# Array-Sensors.net
KiCad netlist of a schematic drawn in Altium Designer
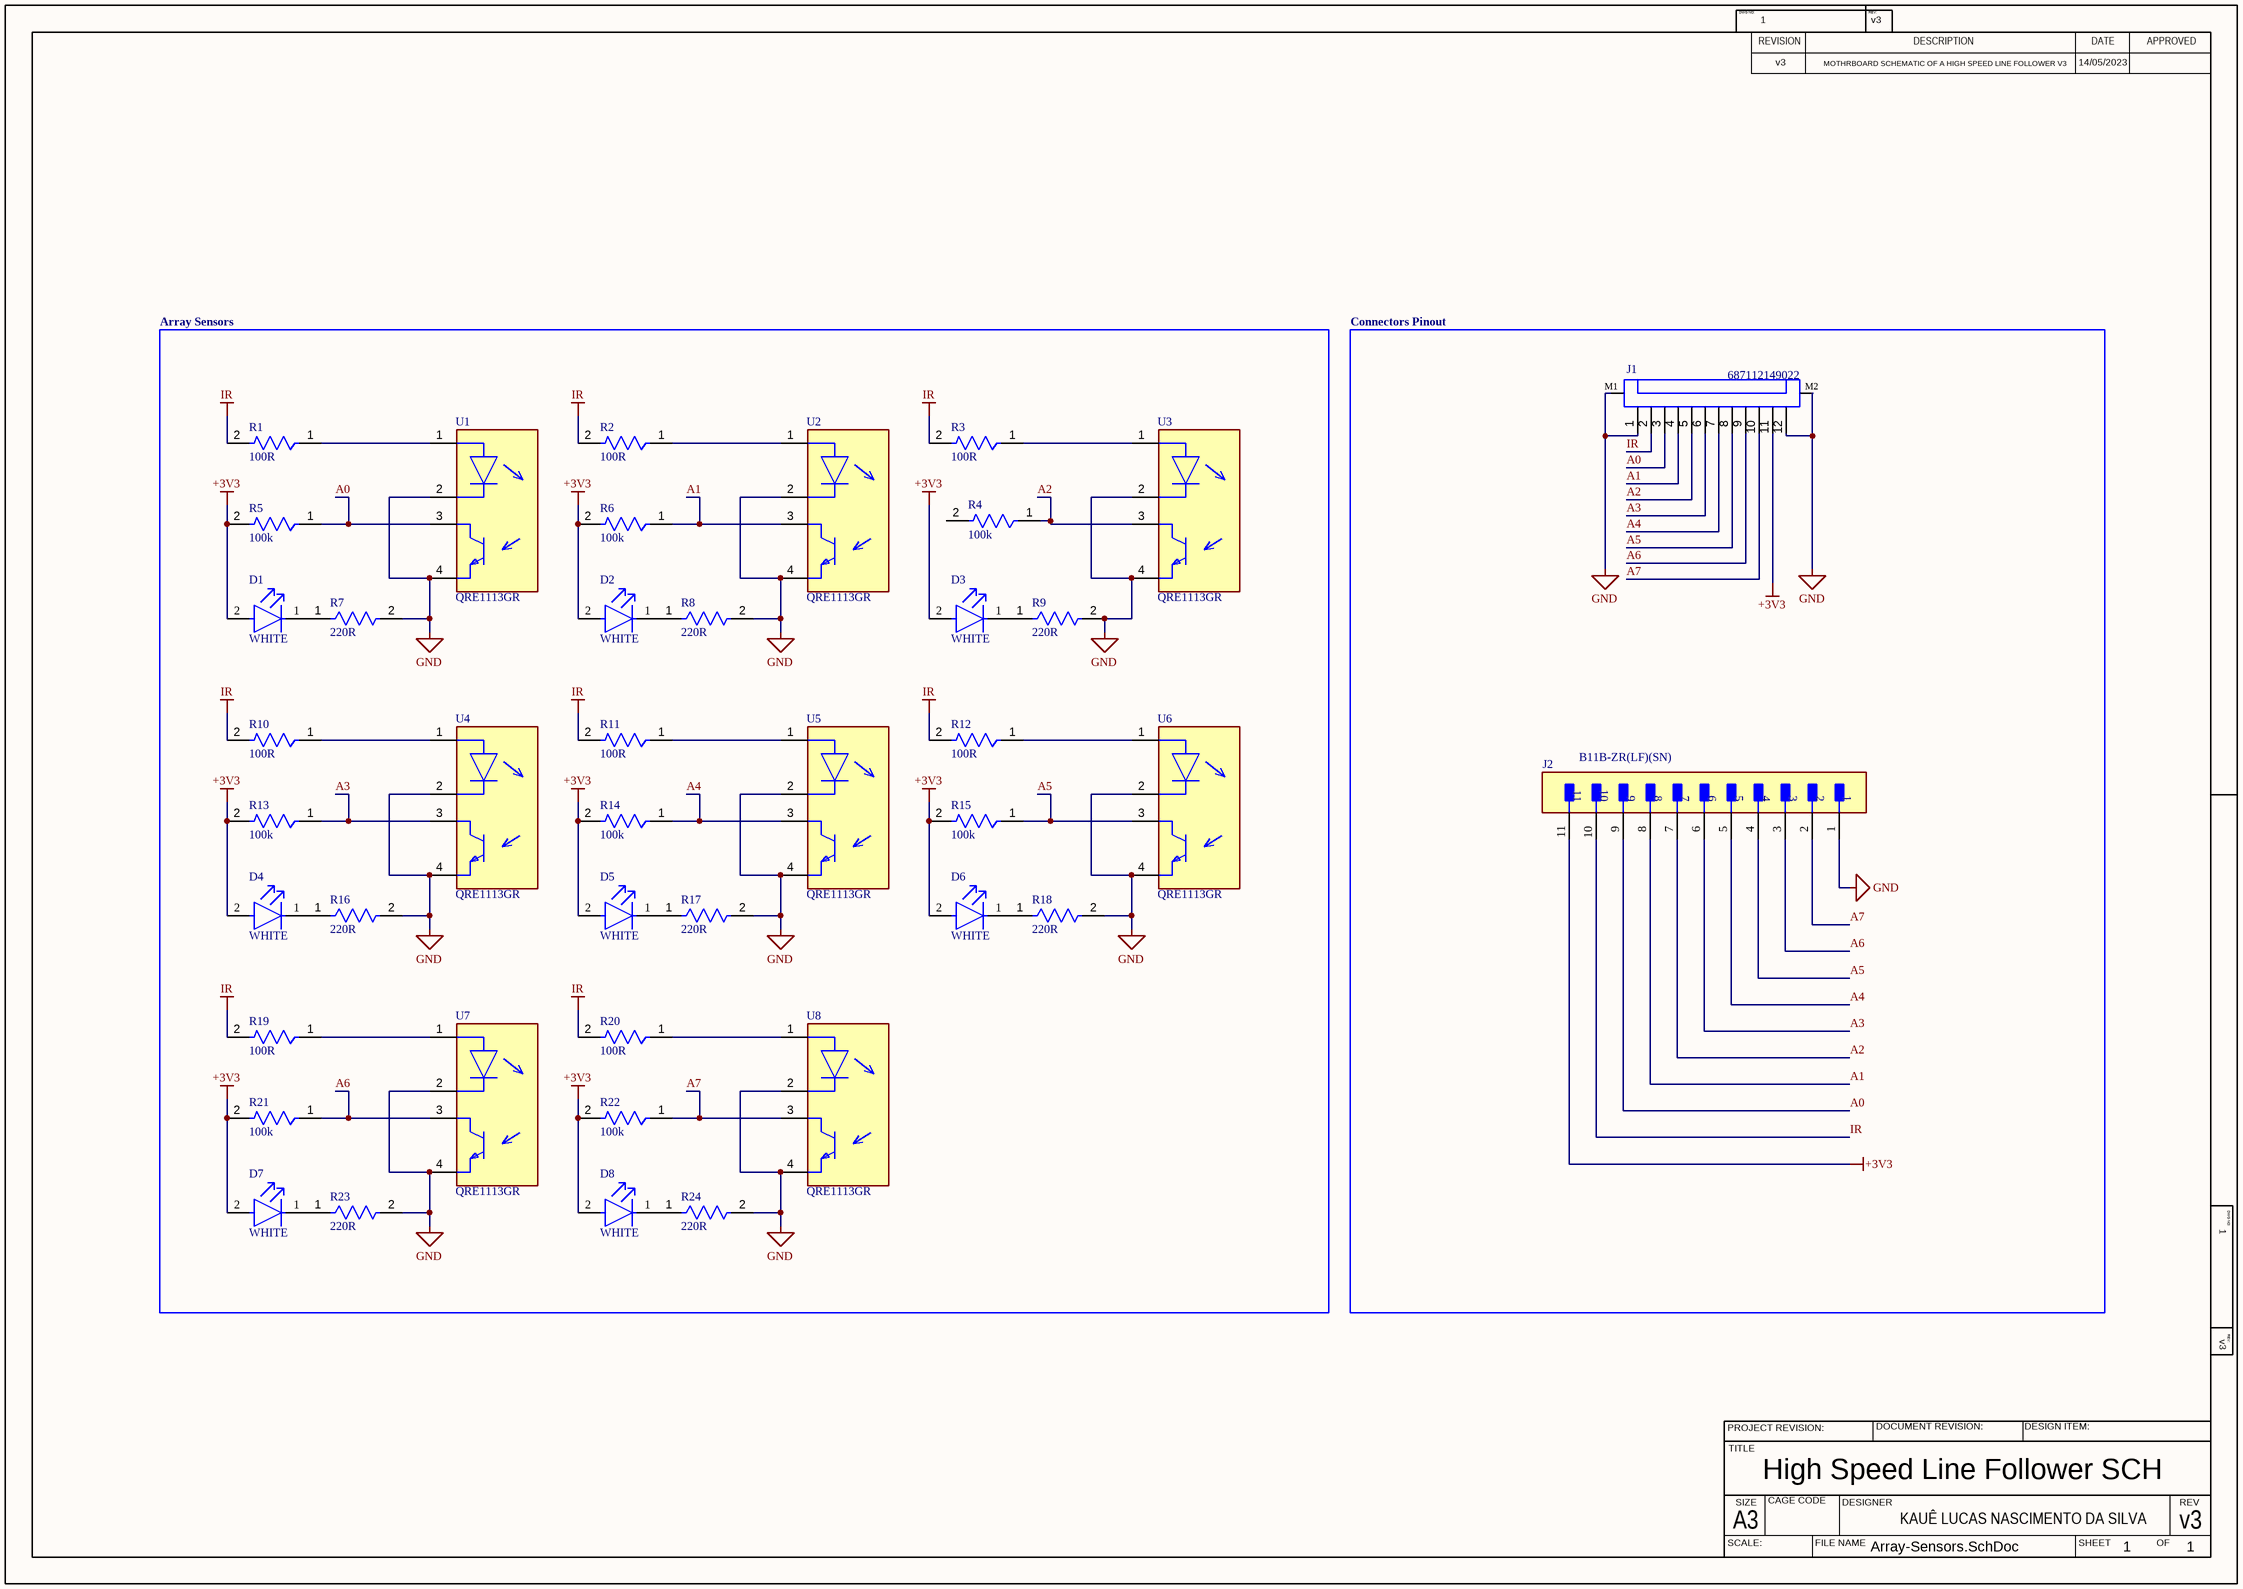
[diagram p0: Array-Sensors.SchDoc]

(export (version "E")
  (design (tool "Eeschema 10.0.6"))
  (components
    (comp (ref "D1")
      (value "WHITE")
      (footprint "FP-SML-LX0805UWC-TR-MFG")
      (description "SML-LX0805UWC-TR White LED, 0805 Diffused, Rectangle Lens SMD package")
      (libsource (lib "Altium Content Vault") (part "8706943c75ba83719d021d2fdc84c58"))
    )
    (comp (ref "D2")
      (value "WHITE")
      (footprint "FP-SML-LX0805UWC-TR-MFG")
      (description "SML-LX0805UWC-TR White LED, 0805 Diffused, Rectangle Lens SMD package")
      (libsource (lib "Altium Content Vault") (part "8706943c75ba83719d021d2fdc84c58"))
    )
    (comp (ref "D3")
      (value "WHITE")
      (footprint "FP-SML-LX0805UWC-TR-MFG")
      (description "SML-LX0805UWC-TR White LED, 0805 Diffused, Rectangle Lens SMD package")
      (libsource (lib "Altium Content Vault") (part "8706943c75ba83719d021d2fdc84c58"))
    )
    (comp (ref "D4")
      (value "WHITE")
      (footprint "FP-SML-LX0805UWC-TR-MFG")
      (description "SML-LX0805UWC-TR White LED, 0805 Diffused, Rectangle Lens SMD package")
      (libsource (lib "Altium Content Vault") (part "8706943c75ba83719d021d2fdc84c58"))
    )
    (comp (ref "D5")
      (value "WHITE")
      (footprint "FP-SML-LX0805UWC-TR-MFG")
      (description "SML-LX0805UWC-TR White LED, 0805 Diffused, Rectangle Lens SMD package")
      (libsource (lib "Altium Content Vault") (part "8706943c75ba83719d021d2fdc84c58"))
    )
    (comp (ref "D6")
      (value "WHITE")
      (footprint "FP-SML-LX0805UWC-TR-MFG")
      (description "SML-LX0805UWC-TR White LED, 0805 Diffused, Rectangle Lens SMD package")
      (libsource (lib "Altium Content Vault") (part "8706943c75ba83719d021d2fdc84c58"))
    )
    (comp (ref "D7")
      (value "WHITE")
      (footprint "FP-SML-LX0805UWC-TR-MFG")
      (description "SML-LX0805UWC-TR White LED, 0805 Diffused, Rectangle Lens SMD package")
      (libsource (lib "Altium Content Vault") (part "8706943c75ba83719d021d2fdc84c58"))
    )
    (comp (ref "D8")
      (value "WHITE")
      (footprint "FP-SML-LX0805UWC-TR-MFG")
      (description "SML-LX0805UWC-TR White LED, 0805 Diffused, Rectangle Lens SMD package")
      (libsource (lib "Altium Content Vault") (part "8706943c75ba83719d021d2fdc84c58"))
    )
    (comp (ref "J1")
      (value "687112149022")
      (footprint "687112149022")
      (description "FFC/FPC Connector, 12 Contact(s), 1 Row(s), Female, Right Angle, Surface Mount Terminal")
      (libsource (lib "Altium Content Vault") (part "FPC - 12P - 2MP"))
    )
    (comp (ref "J2")
      (value "B11B-ZR(LF)(SN)")
      (footprint "FP-B11B-ZR_LF_SN-MFG")
      (libsource (lib "Altium Content Vault") (part "f29d4bf112d7e9a430f8be9e77fc91e"))
    )
    (comp (ref "R1")
      (value "100R")
      (footprint "FP-AF0805-IPC_A")
      (description "Anti-Sulfurated Chip Resistor Automotive Grade 100Ω 5% 0.125W ±100ppm/°C 0805")
      (fields (field (name "TOLERANCE") "5%"))
      (libsource (lib "Altium Content Vault") (part "1029c3af85768c4190bb7ad29bc67b5"))
    )
    (comp (ref "R2")
      (value "100R")
      (footprint "FP-AF0805-IPC_A")
      (description "Anti-Sulfurated Chip Resistor Automotive Grade 100Ω 5% 0.125W ±100ppm/°C 0805")
      (fields (field (name "TOLERANCE") "5%"))
      (libsource (lib "Altium Content Vault") (part "1029c3af85768c4190bb7ad29bc67b5"))
    )
    (comp (ref "R3")
      (value "100R")
      (footprint "FP-AF0805-IPC_A")
      (description "Anti-Sulfurated Chip Resistor Automotive Grade 100Ω 5% 0.125W ±100ppm/°C 0805")
      (fields (field (name "TOLERANCE") "5%"))
      (libsource (lib "Altium Content Vault") (part "1029c3af85768c4190bb7ad29bc67b5"))
    )
    (comp (ref "R4")
      (value "100k")
      (footprint "FP-CRCW0805-HPe3-MFG")
      (description "RES Thick Film, 100kΩ, 5%, 0.5W, 200ppm/°C, 0805")
      (fields (field (name "TOLERANCE") "5%"))
      (libsource (lib "Altium Content Vault") (part "1029c3af85768c4190bb7ad29bc67b5"))
    )
    (comp (ref "R5")
      (value "100k")
      (footprint "FP-CRCW0805-HPe3-MFG")
      (description "RES Thick Film, 100kΩ, 5%, 0.5W, 200ppm/°C, 0805")
      (fields (field (name "TOLERANCE") "5%"))
      (libsource (lib "Altium Content Vault") (part "1029c3af85768c4190bb7ad29bc67b5"))
    )
    (comp (ref "R6")
      (value "100k")
      (footprint "FP-CRCW0805-HPe3-MFG")
      (description "RES Thick Film, 100kΩ, 5%, 0.5W, 200ppm/°C, 0805")
      (fields (field (name "TOLERANCE") "5%"))
      (libsource (lib "Altium Content Vault") (part "1029c3af85768c4190bb7ad29bc67b5"))
    )
    (comp (ref "R7")
      (value "220R")
      (footprint "FP-AC0805-MFG")
      (description "RES SMD 220 OHM 5% 1/8W 0805")
      (fields
        (field (name "OCTOPART") "https://octopart.com/ac0805jr-07220rl-yageo-30510975")
        (field (name "MANUFACTURER") "Yageo")
      )
      (libsource (lib "Altium Content Vault") (part "1029c3af85768c4190bb7ad29bc67b5"))
    )
    (comp (ref "R8")
      (value "220R")
      (footprint "FP-AC0805-MFG")
      (description "RES SMD 220 OHM 5% 1/8W 0805")
      (fields
        (field (name "OCTOPART") "https://octopart.com/ac0805jr-07220rl-yageo-30510975")
        (field (name "MANUFACTURER") "Yageo")
      )
      (libsource (lib "Altium Content Vault") (part "1029c3af85768c4190bb7ad29bc67b5"))
    )
    (comp (ref "R9")
      (value "220R")
      (footprint "FP-AC0805-MFG")
      (description "RES SMD 220 OHM 5% 1/8W 0805")
      (fields
        (field (name "OCTOPART") "https://octopart.com/ac0805jr-07220rl-yageo-30510975")
        (field (name "MANUFACTURER") "Yageo")
      )
      (libsource (lib "Altium Content Vault") (part "1029c3af85768c4190bb7ad29bc67b5"))
    )
    (comp (ref "R10")
      (value "100R")
      (footprint "FP-AF0805-IPC_A")
      (description "Anti-Sulfurated Chip Resistor Automotive Grade 100Ω 5% 0.125W ±100ppm/°C 0805")
      (fields (field (name "TOLERANCE") "5%"))
      (libsource (lib "Altium Content Vault") (part "1029c3af85768c4190bb7ad29bc67b5"))
    )
    (comp (ref "R11")
      (value "100R")
      (footprint "FP-AF0805-IPC_A")
      (description "Anti-Sulfurated Chip Resistor Automotive Grade 100Ω 5% 0.125W ±100ppm/°C 0805")
      (fields (field (name "TOLERANCE") "5%"))
      (libsource (lib "Altium Content Vault") (part "1029c3af85768c4190bb7ad29bc67b5"))
    )
    (comp (ref "R12")
      (value "100R")
      (footprint "FP-AF0805-IPC_A")
      (description "Anti-Sulfurated Chip Resistor Automotive Grade 100Ω 5% 0.125W ±100ppm/°C 0805")
      (fields (field (name "TOLERANCE") "5%"))
      (libsource (lib "Altium Content Vault") (part "1029c3af85768c4190bb7ad29bc67b5"))
    )
    (comp (ref "R13")
      (value "100k")
      (footprint "FP-CRCW0805-HPe3-MFG")
      (description "RES Thick Film, 100kΩ, 5%, 0.5W, 200ppm/°C, 0805")
      (fields (field (name "TOLERANCE") "5%"))
      (libsource (lib "Altium Content Vault") (part "1029c3af85768c4190bb7ad29bc67b5"))
    )
    (comp (ref "R14")
      (value "100k")
      (footprint "FP-CRCW0805-HPe3-MFG")
      (description "RES Thick Film, 100kΩ, 5%, 0.5W, 200ppm/°C, 0805")
      (fields (field (name "TOLERANCE") "5%"))
      (libsource (lib "Altium Content Vault") (part "1029c3af85768c4190bb7ad29bc67b5"))
    )
    (comp (ref "R15")
      (value "100k")
      (footprint "FP-CRCW0805-HPe3-MFG")
      (description "RES Thick Film, 100kΩ, 5%, 0.5W, 200ppm/°C, 0805")
      (fields (field (name "TOLERANCE") "5%"))
      (libsource (lib "Altium Content Vault") (part "1029c3af85768c4190bb7ad29bc67b5"))
    )
    (comp (ref "R16")
      (value "220R")
      (footprint "FP-AC0805-MFG")
      (description "RES SMD 220 OHM 5% 1/8W 0805")
      (fields
        (field (name "OCTOPART") "https://octopart.com/ac0805jr-07220rl-yageo-30510975")
        (field (name "MANUFACTURER") "Yageo")
      )
      (libsource (lib "Altium Content Vault") (part "1029c3af85768c4190bb7ad29bc67b5"))
    )
    (comp (ref "R17")
      (value "220R")
      (footprint "FP-AC0805-MFG")
      (description "RES SMD 220 OHM 5% 1/8W 0805")
      (fields
        (field (name "OCTOPART") "https://octopart.com/ac0805jr-07220rl-yageo-30510975")
        (field (name "MANUFACTURER") "Yageo")
      )
      (libsource (lib "Altium Content Vault") (part "1029c3af85768c4190bb7ad29bc67b5"))
    )
    (comp (ref "R18")
      (value "220R")
      (footprint "FP-AC0805-MFG")
      (description "RES SMD 220 OHM 5% 1/8W 0805")
      (fields
        (field (name "OCTOPART") "https://octopart.com/ac0805jr-07220rl-yageo-30510975")
        (field (name "MANUFACTURER") "Yageo")
      )
      (libsource (lib "Altium Content Vault") (part "1029c3af85768c4190bb7ad29bc67b5"))
    )
    (comp (ref "R19")
      (value "100R")
      (footprint "FP-AF0805-IPC_A")
      (description "Anti-Sulfurated Chip Resistor Automotive Grade 100Ω 5% 0.125W ±100ppm/°C 0805")
      (fields (field (name "TOLERANCE") "5%"))
      (libsource (lib "Altium Content Vault") (part "1029c3af85768c4190bb7ad29bc67b5"))
    )
    (comp (ref "R20")
      (value "100R")
      (footprint "FP-AF0805-IPC_A")
      (description "Anti-Sulfurated Chip Resistor Automotive Grade 100Ω 5% 0.125W ±100ppm/°C 0805")
      (fields (field (name "TOLERANCE") "5%"))
      (libsource (lib "Altium Content Vault") (part "1029c3af85768c4190bb7ad29bc67b5"))
    )
    (comp (ref "R21")
      (value "100k")
      (footprint "FP-CRCW0805-HPe3-MFG")
      (description "RES Thick Film, 100kΩ, 5%, 0.5W, 200ppm/°C, 0805")
      (fields (field (name "TOLERANCE") "5%"))
      (libsource (lib "Altium Content Vault") (part "1029c3af85768c4190bb7ad29bc67b5"))
    )
    (comp (ref "R22")
      (value "100k")
      (footprint "FP-CRCW0805-HPe3-MFG")
      (description "RES Thick Film, 100kΩ, 5%, 0.5W, 200ppm/°C, 0805")
      (fields (field (name "TOLERANCE") "5%"))
      (libsource (lib "Altium Content Vault") (part "1029c3af85768c4190bb7ad29bc67b5"))
    )
    (comp (ref "R23")
      (value "220R")
      (footprint "FP-AC0805-MFG")
      (description "RES SMD 220 OHM 5% 1/8W 0805")
      (fields
        (field (name "OCTOPART") "https://octopart.com/ac0805jr-07220rl-yageo-30510975")
        (field (name "MANUFACTURER") "Yageo")
      )
      (libsource (lib "Altium Content Vault") (part "1029c3af85768c4190bb7ad29bc67b5"))
    )
    (comp (ref "R24")
      (value "220R")
      (footprint "FP-AC0805-MFG")
      (description "RES SMD 220 OHM 5% 1/8W 0805")
      (fields
        (field (name "OCTOPART") "https://octopart.com/ac0805jr-07220rl-yageo-30510975")
        (field (name "MANUFACTURER") "Yageo")
      )
      (libsource (lib "Altium Content Vault") (part "1029c3af85768c4190bb7ad29bc67b5"))
    )
    (comp (ref "U1")
      (value "QRE1113GR")
      (footprint "FP-100CY-MFG")
      (description "SENSOR OPTO TRANS REFL SMD PHOTO")
      (libsource (lib "Altium Content Vault") (part "7f7a55cf1778c7f4ea4f35509e0890d"))
    )
    (comp (ref "U2")
      (value "QRE1113GR")
      (footprint "FP-100CY-MFG")
      (description "SENSOR OPTO TRANS REFL SMD PHOTO")
      (libsource (lib "Altium Content Vault") (part "7f7a55cf1778c7f4ea4f35509e0890d"))
    )
    (comp (ref "U3")
      (value "QRE1113GR")
      (footprint "FP-100CY-MFG")
      (description "SENSOR OPTO TRANS REFL SMD PHOTO")
      (libsource (lib "Altium Content Vault") (part "7f7a55cf1778c7f4ea4f35509e0890d"))
    )
    (comp (ref "U4")
      (value "QRE1113GR")
      (footprint "FP-100CY-MFG")
      (description "SENSOR OPTO TRANS REFL SMD PHOTO")
      (libsource (lib "Altium Content Vault") (part "7f7a55cf1778c7f4ea4f35509e0890d"))
    )
    (comp (ref "U5")
      (value "QRE1113GR")
      (footprint "FP-100CY-MFG")
      (description "SENSOR OPTO TRANS REFL SMD PHOTO")
      (libsource (lib "Altium Content Vault") (part "7f7a55cf1778c7f4ea4f35509e0890d"))
    )
    (comp (ref "U6")
      (value "QRE1113GR")
      (footprint "FP-100CY-MFG")
      (description "SENSOR OPTO TRANS REFL SMD PHOTO")
      (libsource (lib "Altium Content Vault") (part "7f7a55cf1778c7f4ea4f35509e0890d"))
    )
    (comp (ref "U7")
      (value "QRE1113GR")
      (footprint "FP-100CY-MFG")
      (description "SENSOR OPTO TRANS REFL SMD PHOTO")
      (libsource (lib "Altium Content Vault") (part "7f7a55cf1778c7f4ea4f35509e0890d"))
    )
    (comp (ref "U8")
      (value "QRE1113GR")
      (footprint "FP-100CY-MFG")
      (description "SENSOR OPTO TRANS REFL SMD PHOTO")
      (libsource (lib "Altium Content Vault") (part "7f7a55cf1778c7f4ea4f35509e0890d"))
    )
  )
  (nets
    (net (code "1") (name "+3V3") (class "Default")
      (node (ref "D1") (pin "2") (pinfunction "A_2") (pintype "passive"))
      (node (ref "D2") (pin "2") (pinfunction "A_2") (pintype "passive"))
      (node (ref "D3") (pin "2") (pinfunction "A_2") (pintype "passive"))
      (node (ref "D4") (pin "2") (pinfunction "A_2") (pintype "passive"))
      (node (ref "D5") (pin "2") (pinfunction "A_2") (pintype "passive"))
      (node (ref "D6") (pin "2") (pinfunction "A_2") (pintype "passive"))
      (node (ref "D7") (pin "2") (pinfunction "A_2") (pintype "passive"))
      (node (ref "D8") (pin "2") (pinfunction "A_2") (pintype "passive"))
      (node (ref "J1") (pin "11") (pinfunction "11_11") (pintype "passive"))
      (node (ref "J2") (pin "11") (pinfunction "11_11") (pintype "passive"))
      (node (ref "R13") (pin "2") (pinfunction "2_2") (pintype "passive"))
      (node (ref "R14") (pin "2") (pinfunction "2_2") (pintype "passive"))
      (node (ref "R15") (pin "2") (pinfunction "2_2") (pintype "passive"))
      (node (ref "R21") (pin "2") (pinfunction "2_2") (pintype "passive"))
      (node (ref "R22") (pin "2") (pinfunction "2_2") (pintype "passive"))
      (node (ref "R5") (pin "2") (pinfunction "2_2") (pintype "passive"))
      (node (ref "R6") (pin "2") (pinfunction "2_2") (pintype "passive"))
    )
    (net (code "2") (name "/A0") (class "Default")
      (node (ref "J1") (pin "3") (pinfunction "3_3") (pintype "passive"))
      (node (ref "J2") (pin "9") (pinfunction "9_9") (pintype "passive"))
      (node (ref "R5") (pin "1") (pinfunction "1_1") (pintype "passive"))
      (node (ref "U1") (pin "3") (pinfunction "C_3") (pintype "passive"))
    )
    (net (code "3") (name "/A1") (class "Default")
      (node (ref "J1") (pin "4") (pinfunction "4_4") (pintype "passive"))
      (node (ref "J2") (pin "8") (pinfunction "8_8") (pintype "passive"))
      (node (ref "R6") (pin "1") (pinfunction "1_1") (pintype "passive"))
      (node (ref "U2") (pin "3") (pinfunction "C_3") (pintype "passive"))
    )
    (net (code "4") (name "/A2") (class "Default")
      (node (ref "J1") (pin "5") (pinfunction "5_5") (pintype "passive"))
      (node (ref "J2") (pin "7") (pinfunction "7_7") (pintype "passive"))
      (node (ref "R4") (pin "1") (pinfunction "1_1") (pintype "passive"))
      (node (ref "U3") (pin "3") (pinfunction "C_3") (pintype "passive"))
    )
    (net (code "5") (name "/A3") (class "Default")
      (node (ref "J1") (pin "6") (pinfunction "6_6") (pintype "passive"))
      (node (ref "J2") (pin "6") (pinfunction "6_6") (pintype "passive"))
      (node (ref "R13") (pin "1") (pinfunction "1_1") (pintype "passive"))
      (node (ref "U4") (pin "3") (pinfunction "C_3") (pintype "passive"))
    )
    (net (code "6") (name "/A4") (class "Default")
      (node (ref "J1") (pin "7") (pinfunction "7_7") (pintype "passive"))
      (node (ref "J2") (pin "5") (pinfunction "5_5") (pintype "passive"))
      (node (ref "R14") (pin "1") (pinfunction "1_1") (pintype "passive"))
      (node (ref "U5") (pin "3") (pinfunction "C_3") (pintype "passive"))
    )
    (net (code "7") (name "/A5") (class "Default")
      (node (ref "J1") (pin "8") (pinfunction "8_8") (pintype "passive"))
      (node (ref "J2") (pin "4") (pinfunction "4_4") (pintype "passive"))
      (node (ref "R15") (pin "1") (pinfunction "1_1") (pintype "passive"))
      (node (ref "U6") (pin "3") (pinfunction "C_3") (pintype "passive"))
    )
    (net (code "8") (name "/A6") (class "Default")
      (node (ref "J1") (pin "9") (pinfunction "9_9") (pintype "passive"))
      (node (ref "J2") (pin "3") (pinfunction "3_3") (pintype "passive"))
      (node (ref "R21") (pin "1") (pinfunction "1_1") (pintype "passive"))
      (node (ref "U7") (pin "3") (pinfunction "C_3") (pintype "passive"))
    )
    (net (code "9") (name "/A7") (class "Default")
      (node (ref "J1") (pin "10") (pinfunction "10_10") (pintype "passive"))
      (node (ref "J2") (pin "2") (pinfunction "2_2") (pintype "passive"))
      (node (ref "R22") (pin "1") (pinfunction "1_1") (pintype "passive"))
      (node (ref "U8") (pin "3") (pinfunction "C_3") (pintype "passive"))
    )
    (net (code "10") (name "GND") (class "Default")
      (node (ref "J1") (pin "1") (pinfunction "1_1") (pintype "passive"))
      (node (ref "J1") (pin "12") (pinfunction "12_12") (pintype "passive"))
      (node (ref "J1") (pin "M1") (pinfunction "M1_M1") (pintype "passive"))
      (node (ref "J1") (pin "M2") (pinfunction "M2_M2") (pintype "passive"))
      (node (ref "J2") (pin "1") (pinfunction "1_1") (pintype "passive"))
      (node (ref "R16") (pin "2") (pinfunction "2_2") (pintype "passive"))
      (node (ref "R17") (pin "2") (pinfunction "2_2") (pintype "passive"))
      (node (ref "R18") (pin "2") (pinfunction "2_2") (pintype "passive"))
      (node (ref "R23") (pin "2") (pinfunction "2_2") (pintype "passive"))
      (node (ref "R24") (pin "2") (pinfunction "2_2") (pintype "passive"))
      (node (ref "R7") (pin "2") (pinfunction "2_2") (pintype "passive"))
      (node (ref "R8") (pin "2") (pinfunction "2_2") (pintype "passive"))
      (node (ref "R9") (pin "2") (pinfunction "2_2") (pintype "passive"))
      (node (ref "U1") (pin "2") (pinfunction "C_2") (pintype "passive"))
      (node (ref "U1") (pin "4") (pinfunction "E_4") (pintype "passive"))
      (node (ref "U2") (pin "2") (pinfunction "C_2") (pintype "passive"))
      (node (ref "U2") (pin "4") (pinfunction "E_4") (pintype "passive"))
      (node (ref "U3") (pin "2") (pinfunction "C_2") (pintype "passive"))
      (node (ref "U3") (pin "4") (pinfunction "E_4") (pintype "passive"))
      (node (ref "U4") (pin "2") (pinfunction "C_2") (pintype "passive"))
      (node (ref "U4") (pin "4") (pinfunction "E_4") (pintype "passive"))
      (node (ref "U5") (pin "2") (pinfunction "C_2") (pintype "passive"))
      (node (ref "U5") (pin "4") (pinfunction "E_4") (pintype "passive"))
      (node (ref "U6") (pin "2") (pinfunction "C_2") (pintype "passive"))
      (node (ref "U6") (pin "4") (pinfunction "E_4") (pintype "passive"))
      (node (ref "U7") (pin "2") (pinfunction "C_2") (pintype "passive"))
      (node (ref "U7") (pin "4") (pinfunction "E_4") (pintype "passive"))
      (node (ref "U8") (pin "2") (pinfunction "C_2") (pintype "passive"))
      (node (ref "U8") (pin "4") (pinfunction "E_4") (pintype "passive"))
    )
    (net (code "11") (name "IR") (class "Default")
      (node (ref "J1") (pin "2") (pinfunction "2_2") (pintype "passive"))
      (node (ref "J2") (pin "10") (pinfunction "10_10") (pintype "passive"))
      (node (ref "R1") (pin "2") (pinfunction "2_2") (pintype "passive"))
      (node (ref "R10") (pin "2") (pinfunction "2_2") (pintype "passive"))
      (node (ref "R11") (pin "2") (pinfunction "2_2") (pintype "passive"))
      (node (ref "R12") (pin "2") (pinfunction "2_2") (pintype "passive"))
      (node (ref "R19") (pin "2") (pinfunction "2_2") (pintype "passive"))
      (node (ref "R2") (pin "2") (pinfunction "2_2") (pintype "passive"))
      (node (ref "R20") (pin "2") (pinfunction "2_2") (pintype "passive"))
      (node (ref "R3") (pin "2") (pinfunction "2_2") (pintype "passive"))
    )
    (net (code "12") (name "Net-(D1-C)") (class "Default")
      (node (ref "D1") (pin "1") (pinfunction "C_1") (pintype "passive"))
      (node (ref "R7") (pin "1") (pinfunction "1_1") (pintype "passive"))
    )
    (net (code "13") (name "Net-(D2-C)") (class "Default")
      (node (ref "D2") (pin "1") (pinfunction "C_1") (pintype "passive"))
      (node (ref "R8") (pin "1") (pinfunction "1_1") (pintype "passive"))
    )
    (net (code "14") (name "Net-(D3-C)") (class "Default")
      (node (ref "D3") (pin "1") (pinfunction "C_1") (pintype "passive"))
      (node (ref "R9") (pin "1") (pinfunction "1_1") (pintype "passive"))
    )
    (net (code "15") (name "Net-(D4-C)") (class "Default")
      (node (ref "D4") (pin "1") (pinfunction "C_1") (pintype "passive"))
      (node (ref "R16") (pin "1") (pinfunction "1_1") (pintype "passive"))
    )
    (net (code "16") (name "Net-(D5-C)") (class "Default")
      (node (ref "D5") (pin "1") (pinfunction "C_1") (pintype "passive"))
      (node (ref "R17") (pin "1") (pinfunction "1_1") (pintype "passive"))
    )
    (net (code "17") (name "Net-(D6-C)") (class "Default")
      (node (ref "D6") (pin "1") (pinfunction "C_1") (pintype "passive"))
      (node (ref "R18") (pin "1") (pinfunction "1_1") (pintype "passive"))
    )
    (net (code "18") (name "Net-(D7-C)") (class "Default")
      (node (ref "D7") (pin "1") (pinfunction "C_1") (pintype "passive"))
      (node (ref "R23") (pin "1") (pinfunction "1_1") (pintype "passive"))
    )
    (net (code "19") (name "Net-(D8-C)") (class "Default")
      (node (ref "D8") (pin "1") (pinfunction "C_1") (pintype "passive"))
      (node (ref "R24") (pin "1") (pinfunction "1_1") (pintype "passive"))
    )
    (net (code "20") (name "Net-(U1-A)") (class "Default")
      (node (ref "R1") (pin "1") (pinfunction "1_1") (pintype "passive"))
      (node (ref "U1") (pin "1") (pinfunction "A_1") (pintype "passive"))
    )
    (net (code "21") (name "Net-(U2-A)") (class "Default")
      (node (ref "R2") (pin "1") (pinfunction "1_1") (pintype "passive"))
      (node (ref "U2") (pin "1") (pinfunction "A_1") (pintype "passive"))
    )
    (net (code "22") (name "Net-(U3-A)") (class "Default")
      (node (ref "R3") (pin "1") (pinfunction "1_1") (pintype "passive"))
      (node (ref "U3") (pin "1") (pinfunction "A_1") (pintype "passive"))
    )
    (net (code "23") (name "Net-(U4-A)") (class "Default")
      (node (ref "R10") (pin "1") (pinfunction "1_1") (pintype "passive"))
      (node (ref "U4") (pin "1") (pinfunction "A_1") (pintype "passive"))
    )
    (net (code "24") (name "Net-(U5-A)") (class "Default")
      (node (ref "R11") (pin "1") (pinfunction "1_1") (pintype "passive"))
      (node (ref "U5") (pin "1") (pinfunction "A_1") (pintype "passive"))
    )
    (net (code "25") (name "Net-(U6-A)") (class "Default")
      (node (ref "R12") (pin "1") (pinfunction "1_1") (pintype "passive"))
      (node (ref "U6") (pin "1") (pinfunction "A_1") (pintype "passive"))
    )
    (net (code "26") (name "Net-(U7-A)") (class "Default")
      (node (ref "R19") (pin "1") (pinfunction "1_1") (pintype "passive"))
      (node (ref "U7") (pin "1") (pinfunction "A_1") (pintype "passive"))
    )
    (net (code "27") (name "Net-(U8-A)") (class "Default")
      (node (ref "R20") (pin "1") (pinfunction "1_1") (pintype "passive"))
      (node (ref "U8") (pin "1") (pinfunction "A_1") (pintype "passive"))
    )
    (net (code "28") (name "unconnected-(R4-Pad2)") (class "Default")
      (node (ref "R4") (pin "2") (pinfunction "2_2") (pintype "passive"))
    )
  )
)
